# T5400_Barometer_Breakout-v10.net
KiCad netlist of a schematic drawn in EAGLE
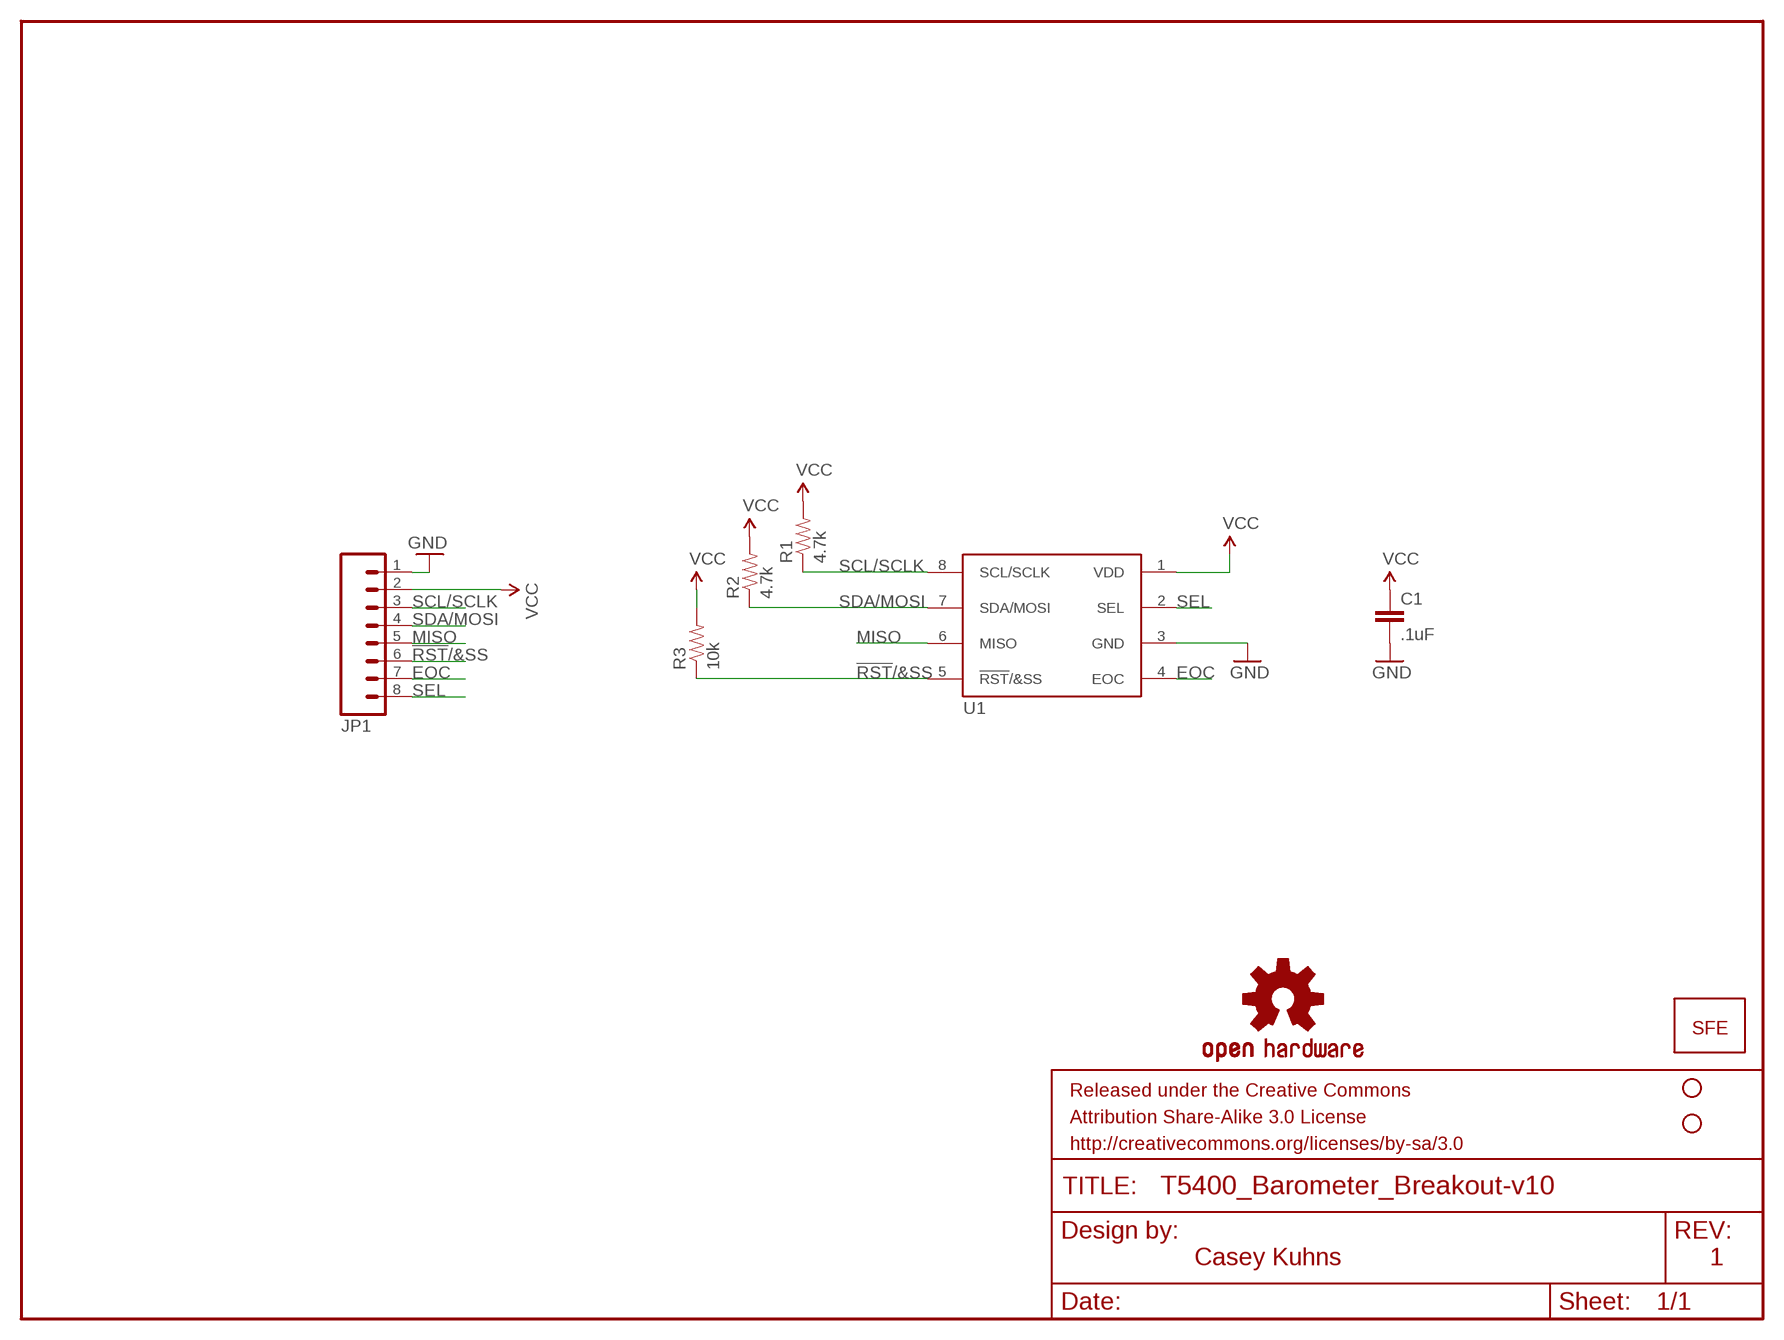
[diagram p0: schematic, sheet 1]

(export (version "E")
  (design (tool "Eeschema 10.0.6"))
  (components
    (comp (ref "C1")
      (value ".1uF")
      (footprint "eagle-import:0603-CAP")
      (libsource (lib "eagle-import") (part "0.1UF-25V-5%(0603)"))
    )
    (comp (ref "FRAME1")
      (value "FRAME-LETTER")
      (footprint "eagle-import:CREATIVE_COMMONS")
      (libsource (lib "eagle-import") (part "FRAME-LETTER"))
    )
    (comp (ref "JP1")
      (value "M081X08")
      (footprint "eagle-import:1X08")
      (libsource (lib "eagle-import") (part "M081X08"))
    )
    (comp (ref "LOGO1")
      (value "LOGO-SFENEW")
      (footprint "eagle-import:SFE-NEW-WEBLOGO")
      (libsource (lib "eagle-import") (part "LOGO-SFENEW"))
    )
    (comp (ref "LOGO2")
      (value "OSHW-LOGOS")
      (footprint "eagle-import:OSHW-LOGO-S")
      (libsource (lib "eagle-import") (part "OSHW-LOGOS"))
    )
    (comp (ref "R1")
      (value "4.7k")
      (footprint "eagle-import:0603-RES")
      (libsource (lib "eagle-import") (part "RESISTOR0603-RES"))
    )
    (comp (ref "R2")
      (value "4.7k")
      (footprint "eagle-import:0603-RES")
      (libsource (lib "eagle-import") (part "RESISTOR0603-RES"))
    )
    (comp (ref "R3")
      (value "10k")
      (footprint "eagle-import:0603-RES")
      (libsource (lib "eagle-import") (part "RESISTOR0603-RES"))
    )
    (comp (ref "STANDOFF1")
      (value "STAND-OFF")
      (footprint "eagle-import:STAND-OFF")
      (libsource (lib "eagle-import") (part "STAND-OFF"))
    )
    (comp (ref "STANDOFF2")
      (value "STAND-OFF")
      (footprint "eagle-import:STAND-OFF")
      (libsource (lib "eagle-import") (part "STAND-OFF"))
    )
    (comp (ref "U1")
      (value "T5400")
      (footprint "eagle-import:T5400")
      (libsource (lib "eagle-import") (part "T5400"))
    )
  )
  (nets
    (net (code "1") (name "/EOC") (class "Default")
      (node (ref "JP1") (pin "7") (pinfunction "7_7") (pintype "passive"))
      (node (ref "U1") (pin "4") (pinfunction "EOC_4") (pintype "bidirectional"))
    )
    (net (code "2") (name "/MISO") (class "Default")
      (node (ref "JP1") (pin "5") (pinfunction "5_5") (pintype "passive"))
      (node (ref "U1") (pin "6") (pinfunction "MISO_6") (pintype "bidirectional"))
    )
    (net (code "3") (name "/SCL{slash}SCLK") (class "Default")
      (node (ref "JP1") (pin "3") (pinfunction "3_3") (pintype "passive"))
      (node (ref "R1") (pin "1") (pinfunction "1_1") (pintype "passive"))
      (node (ref "U1") (pin "8") (pinfunction "SCL/SCLK_8") (pintype "bidirectional"))
    )
    (net (code "4") (name "/SDA{slash}MOSI") (class "Default")
      (node (ref "JP1") (pin "4") (pinfunction "4_4") (pintype "passive"))
      (node (ref "R2") (pin "1") (pinfunction "1_1") (pintype "passive"))
      (node (ref "U1") (pin "7") (pinfunction "SDA/MOSI_7") (pintype "bidirectional"))
    )
    (net (code "5") (name "/SEL") (class "Default")
      (node (ref "JP1") (pin "8") (pinfunction "8_8") (pintype "passive"))
      (node (ref "U1") (pin "2") (pinfunction "SEL_2") (pintype "bidirectional"))
    )
    (net (code "6") (name "/~{RST}{slash}&SS") (class "Default")
      (node (ref "JP1") (pin "6") (pinfunction "6_6") (pintype "passive"))
      (node (ref "R3") (pin "1") (pinfunction "1_1") (pintype "passive"))
      (node (ref "U1") (pin "5") (pinfunction "~{RST}/&SS_5") (pintype "bidirectional"))
    )
    (net (code "7") (name "GND") (class "Default")
      (node (ref "C1") (pin "2") (pinfunction "2_2") (pintype "passive"))
      (node (ref "JP1") (pin "1") (pinfunction "1_1") (pintype "passive"))
      (node (ref "U1") (pin "3") (pinfunction "GND_3") (pintype "bidirectional"))
    )
    (net (code "8") (name "VCC") (class "Default")
      (node (ref "C1") (pin "1") (pinfunction "1_1") (pintype "passive"))
      (node (ref "JP1") (pin "2") (pinfunction "2_2") (pintype "passive"))
      (node (ref "R1") (pin "2") (pinfunction "2_2") (pintype "passive"))
      (node (ref "R2") (pin "2") (pinfunction "2_2") (pintype "passive"))
      (node (ref "R3") (pin "2") (pinfunction "2_2") (pintype "passive"))
      (node (ref "U1") (pin "1") (pinfunction "VDD_1") (pintype "bidirectional"))
    )
  )
)
